# M220B.net
KiCad netlist of a schematic drawn in EAGLE
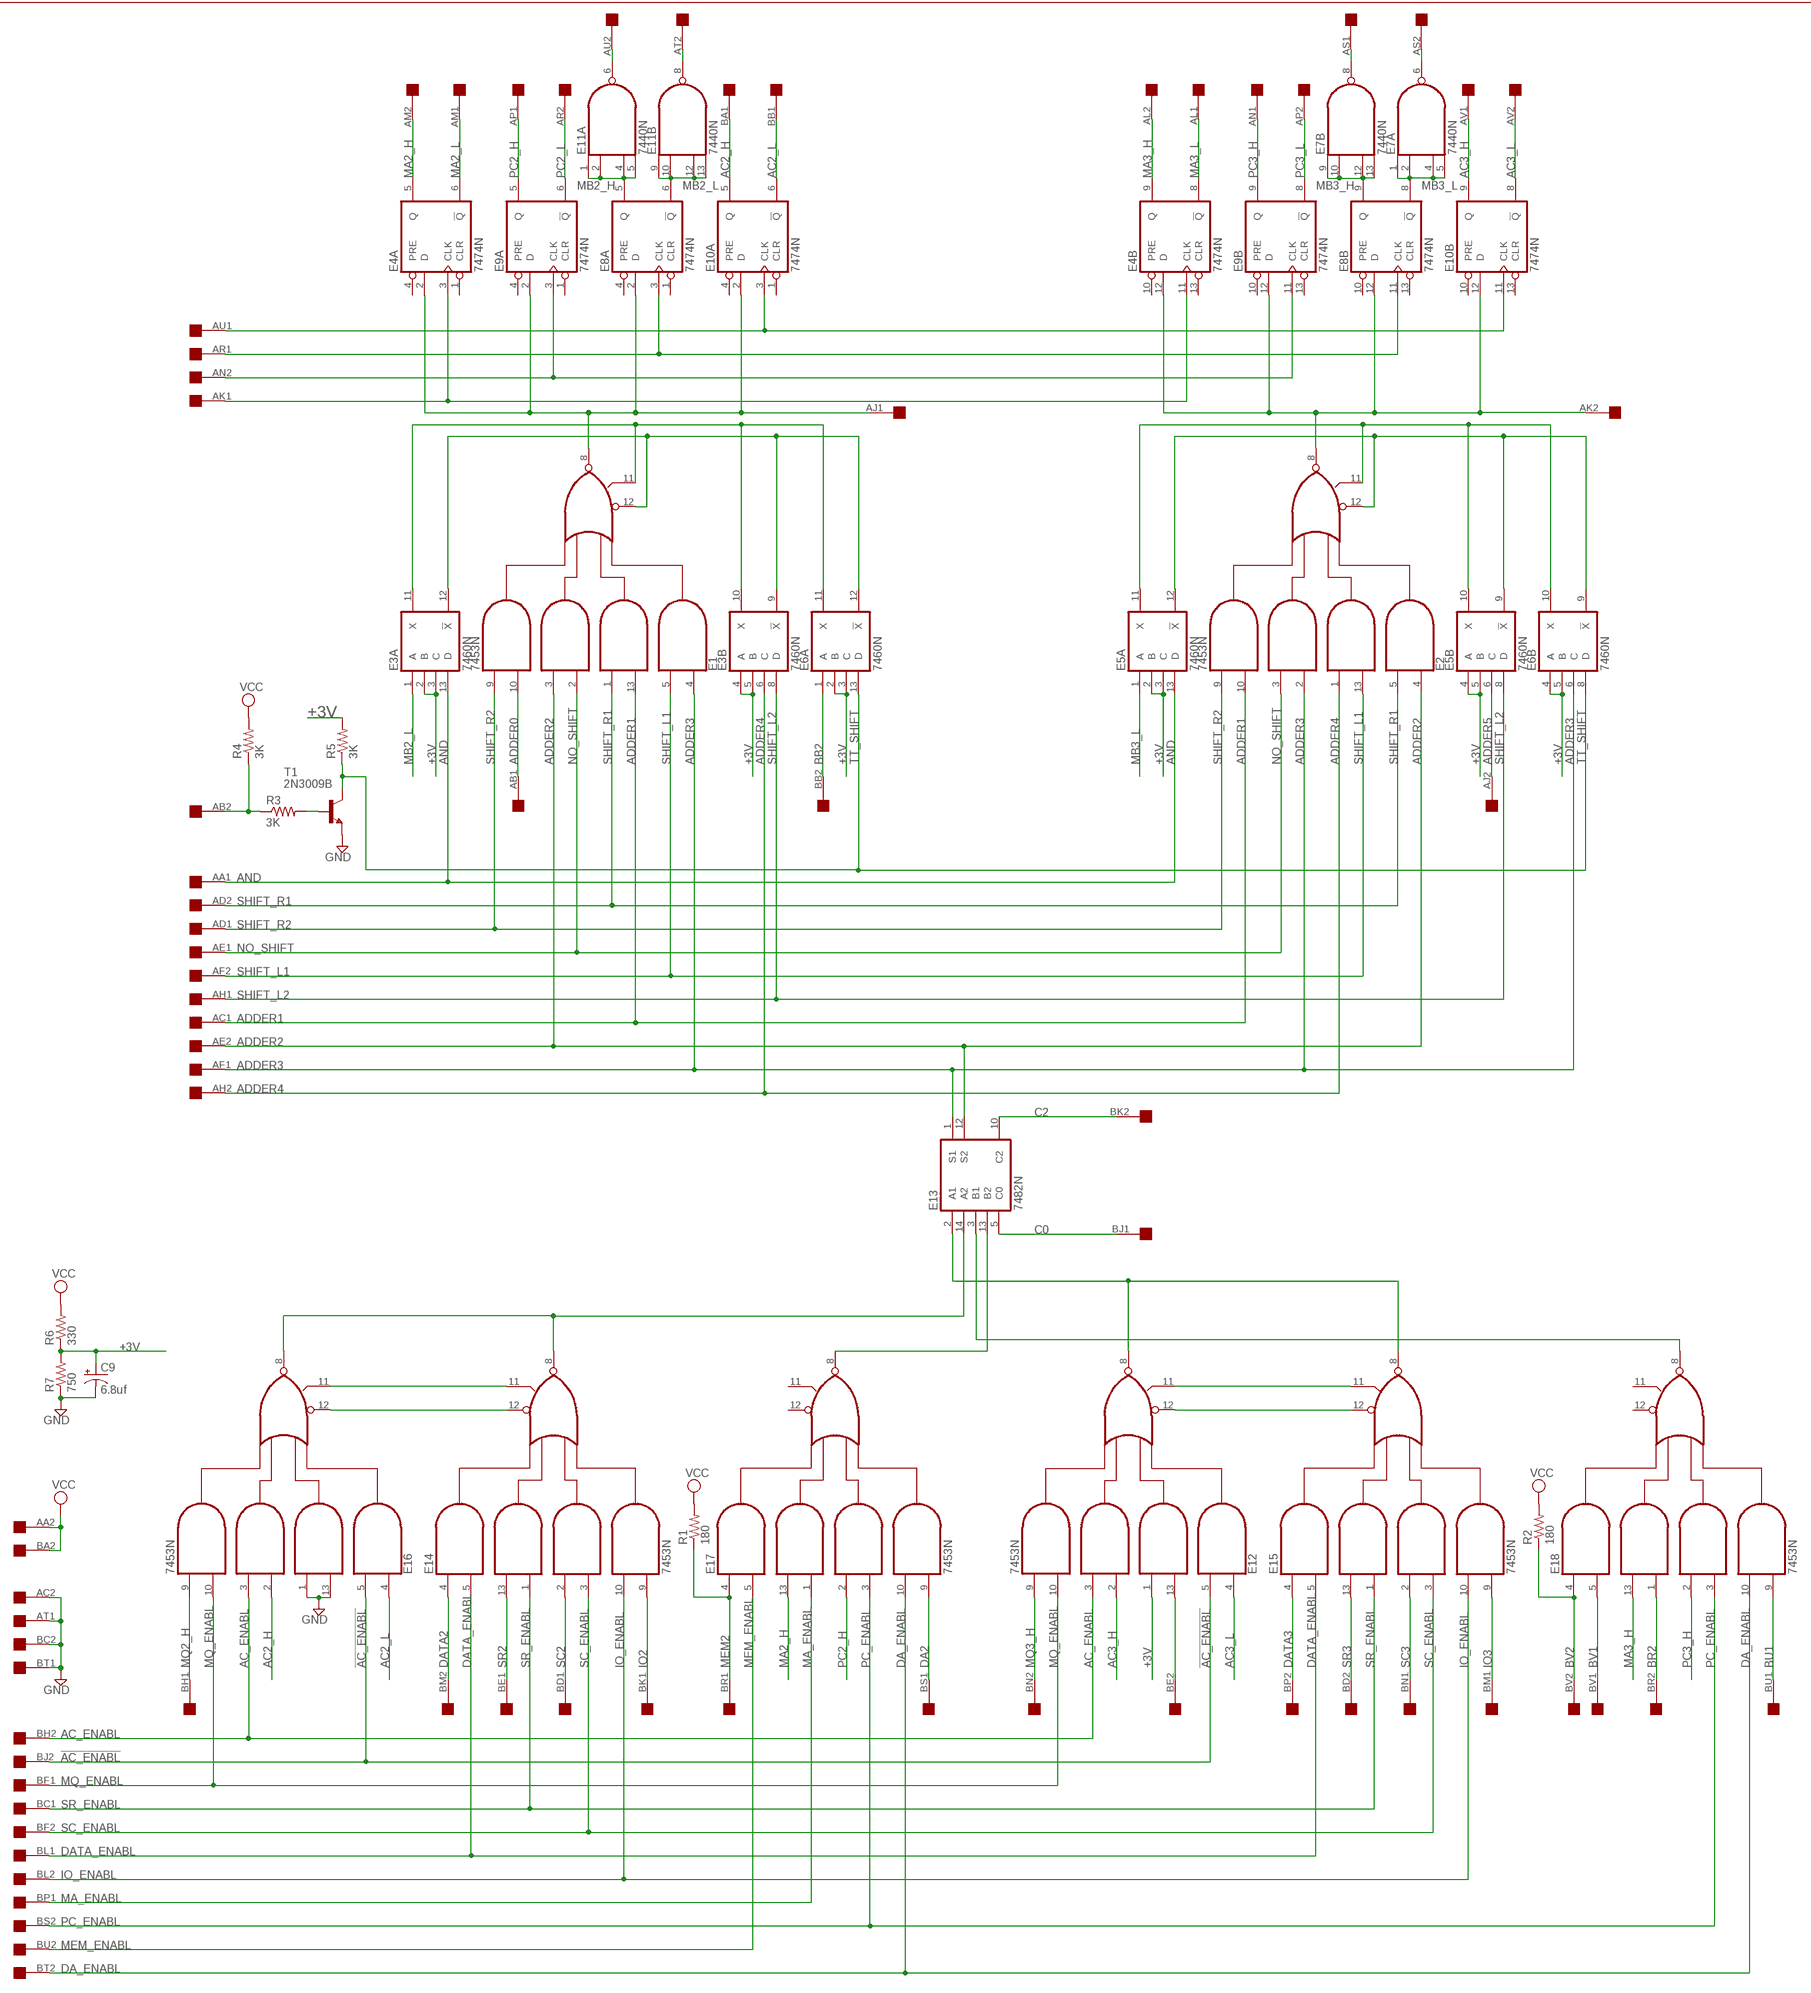
[diagram p0: schematic, sheet 1, part 1 of 2]
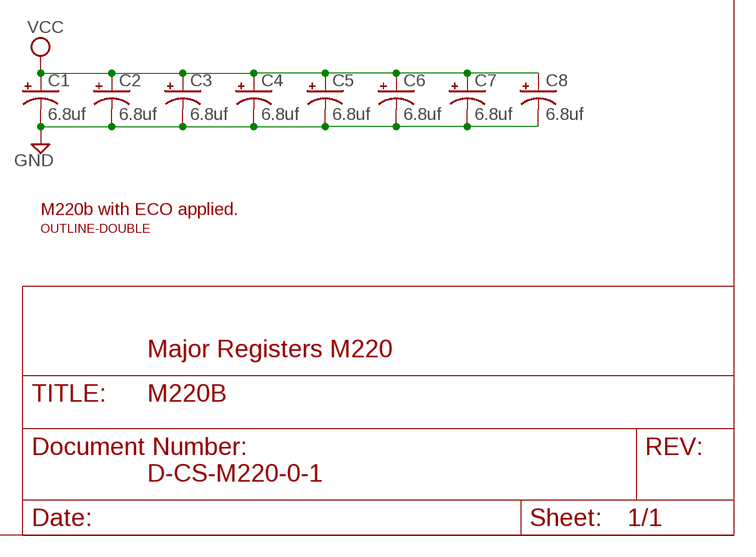
[diagram p1: schematic, sheet 1, part 2 of 2]

(export (version "E")
  (design (tool "Eeschema 10.0.6"))
  (components
    (comp (ref "C1")
      (value "6.8uf")
      (footprint "eagle-import:E15-5")
      (libsource (lib "eagle-import") (part "CPOL-USE15-5AXIAL"))
    )
    (comp (ref "C2")
      (value "6.8uf")
      (footprint "eagle-import:E15-5")
      (libsource (lib "eagle-import") (part "CPOL-USE15-5AXIAL"))
    )
    (comp (ref "C3")
      (value "6.8uf")
      (footprint "eagle-import:E15-5")
      (libsource (lib "eagle-import") (part "CPOL-USE15-5AXIAL"))
    )
    (comp (ref "C4")
      (value "6.8uf")
      (footprint "eagle-import:E15-5")
      (libsource (lib "eagle-import") (part "CPOL-USE15-5AXIAL"))
    )
    (comp (ref "C5")
      (value "6.8uf")
      (footprint "eagle-import:E15-5")
      (libsource (lib "eagle-import") (part "CPOL-USE15-5AXIAL"))
    )
    (comp (ref "C6")
      (value "6.8uf")
      (footprint "eagle-import:E15-5")
      (libsource (lib "eagle-import") (part "CPOL-USE15-5AXIAL"))
    )
    (comp (ref "C7")
      (value "6.8uf")
      (footprint "eagle-import:E15-5")
      (libsource (lib "eagle-import") (part "CPOL-USE15-5AXIAL"))
    )
    (comp (ref "C8")
      (value "6.8uf")
      (footprint "eagle-import:E15-5")
      (libsource (lib "eagle-import") (part "CPOL-USE15-5AXIAL"))
    )
    (comp (ref "C9")
      (value "6.8uf")
      (footprint "eagle-import:E15-5")
      (libsource (lib "eagle-import") (part "rcl_CPOL-USE15-5AXIAL"))
    )
    (comp (ref "E1")
      (value "7453N")
      (footprint "eagle-import:DIL14")
      (libsource (lib "eagle-import") (part "7453N"))
    )
    (comp (ref "E2")
      (value "7453N")
      (footprint "eagle-import:DIL14")
      (libsource (lib "eagle-import") (part "7453N"))
    )
    (comp (ref "E3")
      (value "7460N")
      (footprint "eagle-import:DIL14")
      (libsource (lib "eagle-import") (part "7460N"))
    )
    (comp (ref "E4")
      (value "7474N")
      (footprint "eagle-import:DIL14")
      (libsource (lib "eagle-import") (part "7474NS"))
    )
    (comp (ref "E5")
      (value "7460N")
      (footprint "eagle-import:DIL14")
      (libsource (lib "eagle-import") (part "7460N"))
    )
    (comp (ref "E6")
      (value "7460N")
      (footprint "eagle-import:DIL14")
      (libsource (lib "eagle-import") (part "7460N"))
    )
    (comp (ref "E7")
      (value "7440N")
      (footprint "eagle-import:DIL14")
      (libsource (lib "eagle-import") (part "7420NS"))
    )
    (comp (ref "E8")
      (value "7474N")
      (footprint "eagle-import:DIL14")
      (libsource (lib "eagle-import") (part "7474NS"))
    )
    (comp (ref "E9")
      (value "7474N")
      (footprint "eagle-import:DIL14")
      (libsource (lib "eagle-import") (part "7474NS"))
    )
    (comp (ref "E10")
      (value "7474N")
      (footprint "eagle-import:DIL14")
      (libsource (lib "eagle-import") (part "7474NS"))
    )
    (comp (ref "E11")
      (value "7440N")
      (footprint "eagle-import:DIL14")
      (libsource (lib "eagle-import") (part "7420NS"))
    )
    (comp (ref "E12")
      (value "7453N")
      (footprint "eagle-import:DIL14")
      (libsource (lib "eagle-import") (part "7453N"))
    )
    (comp (ref "E13")
      (value "7482N")
      (footprint "eagle-import:DIL14")
      (libsource (lib "eagle-import") (part "7482N"))
    )
    (comp (ref "E14")
      (value "7453N")
      (footprint "eagle-import:DIL14")
      (libsource (lib "eagle-import") (part "7453N"))
    )
    (comp (ref "E15")
      (value "7453N")
      (footprint "eagle-import:DIL14")
      (libsource (lib "eagle-import") (part "7453N"))
    )
    (comp (ref "E16")
      (value "7453N")
      (footprint "eagle-import:DIL14")
      (libsource (lib "eagle-import") (part "7453N"))
    )
    (comp (ref "E17")
      (value "7453N")
      (footprint "eagle-import:DIL14")
      (libsource (lib "eagle-import") (part "7453N"))
    )
    (comp (ref "E18")
      (value "7453N")
      (footprint "eagle-import:DIL14")
      (libsource (lib "eagle-import") (part "7453N"))
    )
    (comp (ref "R1")
      (value "180")
      (footprint "eagle-import:0207_10")
      (libsource (lib "eagle-import") (part "R-US_0207/10"))
    )
    (comp (ref "R2")
      (value "180")
      (footprint "eagle-import:0207_10")
      (libsource (lib "eagle-import") (part "R-US_0207/10"))
    )
    (comp (ref "R3")
      (value "3K")
      (footprint "eagle-import:0207_10")
      (libsource (lib "eagle-import") (part "R-US_0207/10"))
    )
    (comp (ref "R4")
      (value "3K")
      (footprint "eagle-import:0207_10")
      (libsource (lib "eagle-import") (part "R-US_0207/10"))
    )
    (comp (ref "R5")
      (value "3K")
      (footprint "eagle-import:0207_10")
      (libsource (lib "eagle-import") (part "R-US_0207/10"))
    )
    (comp (ref "R6")
      (value "330")
      (footprint "eagle-import:0207_10")
      (libsource (lib "eagle-import") (part "R-US_0207/10"))
    )
    (comp (ref "R7")
      (value "750")
      (footprint "eagle-import:0207_10")
      (libsource (lib "eagle-import") (part "R-US_0207/10"))
    )
    (comp (ref "T1")
      (value "2N3009B")
      (footprint "eagle-import:TO5")
      (libsource (lib "eagle-import") (part "2N1613"))
    )
    (comp (ref "U$1")
      (value "DOUBLE")
      (footprint "eagle-import:EDGE-CON4")
      (libsource (lib "eagle-import") (part "DOUBLE"))
    )
    (comp (ref "U$2")
      (value "OUTLINE-DOUBLE")
      (footprint "eagle-import:DOUBLE")
      (libsource (lib "eagle-import") (part "OUTLINE-DOUBLE"))
    )
  )
  (nets
    (net (code "1") (name "/+3V") (class "Default")
      (node (ref "C9") (pin "+") (pinfunction "+_+") (pintype "passive"))
      (node (ref "E12") (pin "1") (pinfunction "I4_1") (pintype "input"))
      (node (ref "E3") (pin "2") (pinfunction "B_2") (pintype "input"))
      (node (ref "E3") (pin "3") (pinfunction "C_3") (pintype "input"))
      (node (ref "E3") (pin "4") (pinfunction "A_4") (pintype "input"))
      (node (ref "E3") (pin "5") (pinfunction "B_5") (pintype "input"))
      (node (ref "E5") (pin "2") (pinfunction "B_2") (pintype "input"))
      (node (ref "E5") (pin "3") (pinfunction "C_3") (pintype "input"))
      (node (ref "E5") (pin "4") (pinfunction "A_4") (pintype "input"))
      (node (ref "E5") (pin "5") (pinfunction "B_5") (pintype "input"))
      (node (ref "E6") (pin "2") (pinfunction "B_2") (pintype "input"))
      (node (ref "E6") (pin "3") (pinfunction "C_3") (pintype "input"))
      (node (ref "E6") (pin "4") (pinfunction "A_4") (pintype "input"))
      (node (ref "E6") (pin "5") (pinfunction "B_5") (pintype "input"))
      (node (ref "R5") (pin "2") (pinfunction "2_2") (pintype "passive"))
      (node (ref "R6") (pin "1") (pinfunction "1_1") (pintype "passive"))
      (node (ref "R7") (pin "2") (pinfunction "2_2") (pintype "passive"))
    )
    (net (code "2") (name "/AC2_H") (class "Default")
      (node (ref "E10") (pin "5") (pinfunction "Q_5") (pintype "output"))
      (node (ref "E16") (pin "2") (pinfunction "I5_2") (pintype "input"))
      (node (ref "U$1") (pin "BA1") (pinfunction "1_BA1") (pintype "bidirectional"))
    )
    (net (code "3") (name "/AC2_L") (class "Default")
      (node (ref "E10") (pin "6") (pinfunction "~{Q}_6") (pintype "output"))
      (node (ref "E16") (pin "4") (pinfunction "I1_4") (pintype "input"))
      (node (ref "U$1") (pin "BB1") (pinfunction "1_BB1") (pintype "bidirectional"))
    )
    (net (code "4") (name "/AC3_H") (class "Default")
      (node (ref "E10") (pin "9") (pinfunction "Q_9") (pintype "output"))
      (node (ref "E12") (pin "2") (pinfunction "I5_2") (pintype "input"))
      (node (ref "U$1") (pin "AV1") (pinfunction "1_AV1") (pintype "bidirectional"))
    )
    (net (code "5") (name "/AC3_L") (class "Default")
      (node (ref "E10") (pin "8") (pinfunction "~{Q}_8") (pintype "output"))
      (node (ref "E12") (pin "4") (pinfunction "I1_4") (pintype "input"))
      (node (ref "U$1") (pin "AV2") (pinfunction "1_AV2") (pintype "bidirectional"))
    )
    (net (code "6") (name "/AC_ENABL") (class "Default")
      (node (ref "E12") (pin "3") (pinfunction "I6_3") (pintype "input"))
      (node (ref "E16") (pin "3") (pinfunction "I6_3") (pintype "input"))
      (node (ref "U$1") (pin "BH2") (pinfunction "1_BH2") (pintype "bidirectional"))
    )
    (net (code "7") (name "/ADDER0") (class "Default")
      (node (ref "E1") (pin "10") (pinfunction "I7_10") (pintype "input"))
      (node (ref "U$1") (pin "AB1") (pinfunction "1_AB1") (pintype "bidirectional"))
    )
    (net (code "8") (name "/ADDER1") (class "Default")
      (node (ref "E1") (pin "13") (pinfunction "I3_13") (pintype "input"))
      (node (ref "E2") (pin "10") (pinfunction "I7_10") (pintype "input"))
      (node (ref "U$1") (pin "AC1") (pinfunction "1_AC1") (pintype "bidirectional"))
    )
    (net (code "9") (name "/ADDER2") (class "Default")
      (node (ref "E1") (pin "3") (pinfunction "I6_3") (pintype "input"))
      (node (ref "E13") (pin "12") (pinfunction "S2_12") (pintype "output"))
      (node (ref "E2") (pin "4") (pinfunction "I1_4") (pintype "input"))
      (node (ref "U$1") (pin "AE2") (pinfunction "1_AE2") (pintype "bidirectional"))
    )
    (net (code "10") (name "/ADDER3") (class "Default")
      (node (ref "E1") (pin "4") (pinfunction "I1_4") (pintype "input"))
      (node (ref "E13") (pin "1") (pinfunction "S1_1") (pintype "output"))
      (node (ref "E2") (pin "2") (pinfunction "I5_2") (pintype "input"))
      (node (ref "E6") (pin "6") (pinfunction "C_6") (pintype "input"))
      (node (ref "U$1") (pin "AF1") (pinfunction "1_AF1") (pintype "bidirectional"))
    )
    (net (code "11") (name "/ADDER4") (class "Default")
      (node (ref "E2") (pin "1") (pinfunction "I4_1") (pintype "input"))
      (node (ref "E3") (pin "6") (pinfunction "C_6") (pintype "input"))
      (node (ref "U$1") (pin "AH2") (pinfunction "1_AH2") (pintype "bidirectional"))
    )
    (net (code "12") (name "/ADDER5") (class "Default")
      (node (ref "E5") (pin "6") (pinfunction "C_6") (pintype "input"))
      (node (ref "U$1") (pin "AJ2") (pinfunction "1_AJ2") (pintype "bidirectional"))
    )
    (net (code "13") (name "/AND") (class "Default")
      (node (ref "E3") (pin "13") (pinfunction "D_13") (pintype "input"))
      (node (ref "E5") (pin "13") (pinfunction "D_13") (pintype "input"))
      (node (ref "U$1") (pin "AA1") (pinfunction "1_AA1") (pintype "bidirectional"))
    )
    (net (code "14") (name "/BB2") (class "Default")
      (node (ref "E6") (pin "1") (pinfunction "A_1") (pintype "input"))
      (node (ref "U$1") (pin "BB2") (pinfunction "1_BB2") (pintype "bidirectional"))
    )
    (net (code "15") (name "/BR2") (class "Default")
      (node (ref "E18") (pin "1") (pinfunction "I4_1") (pintype "input"))
      (node (ref "U$1") (pin "BR2") (pinfunction "1_BR2") (pintype "bidirectional"))
    )
    (net (code "16") (name "/BU1") (class "Default")
      (node (ref "E18") (pin "9") (pinfunction "I8_9") (pintype "input"))
      (node (ref "U$1") (pin "BU1") (pinfunction "1_BU1") (pintype "bidirectional"))
    )
    (net (code "17") (name "/BV1") (class "Default")
      (node (ref "E18") (pin "5") (pinfunction "I2_5") (pintype "input"))
      (node (ref "U$1") (pin "BV1") (pinfunction "1_BV1") (pintype "bidirectional"))
    )
    (net (code "18") (name "/BV2") (class "Default")
      (node (ref "E18") (pin "4") (pinfunction "I1_4") (pintype "input"))
      (node (ref "R2") (pin "1") (pinfunction "1_1") (pintype "passive"))
      (node (ref "U$1") (pin "BV2") (pinfunction "1_BV2") (pintype "bidirectional"))
    )
    (net (code "19") (name "/C0") (class "Default")
      (node (ref "E13") (pin "5") (pinfunction "C0_5") (pintype "input"))
      (node (ref "U$1") (pin "BJ1") (pinfunction "1_BJ1") (pintype "bidirectional"))
    )
    (net (code "20") (name "/C2") (class "Default")
      (node (ref "E13") (pin "10") (pinfunction "C2_10") (pintype "output"))
      (node (ref "U$1") (pin "BK2") (pinfunction "1_BK2") (pintype "bidirectional"))
    )
    (net (code "21") (name "/DA2") (class "Default")
      (node (ref "E17") (pin "9") (pinfunction "I8_9") (pintype "input"))
      (node (ref "U$1") (pin "BS1") (pinfunction "1_BS1") (pintype "bidirectional"))
    )
    (net (code "22") (name "/DATA2") (class "Default")
      (node (ref "E14") (pin "4") (pinfunction "I1_4") (pintype "input"))
      (node (ref "U$1") (pin "BM2") (pinfunction "1_BM2") (pintype "bidirectional"))
    )
    (net (code "23") (name "/DATA3") (class "Default")
      (node (ref "E15") (pin "4") (pinfunction "I1_4") (pintype "input"))
      (node (ref "U$1") (pin "BP2") (pinfunction "1_BP2") (pintype "bidirectional"))
    )
    (net (code "24") (name "/DATA_ENABL") (class "Default")
      (node (ref "E14") (pin "5") (pinfunction "I2_5") (pintype "input"))
      (node (ref "E15") (pin "5") (pinfunction "I2_5") (pintype "input"))
      (node (ref "U$1") (pin "BL1") (pinfunction "1_BL1") (pintype "bidirectional"))
    )
    (net (code "25") (name "/DA_ENABL") (class "Default")
      (node (ref "E17") (pin "10") (pinfunction "I7_10") (pintype "input"))
      (node (ref "E18") (pin "10") (pinfunction "I7_10") (pintype "input"))
      (node (ref "U$1") (pin "BT2") (pinfunction "1_BT2") (pintype "bidirectional"))
    )
    (net (code "26") (name "/IO2") (class "Default")
      (node (ref "E14") (pin "9") (pinfunction "I8_9") (pintype "input"))
      (node (ref "U$1") (pin "BK1") (pinfunction "1_BK1") (pintype "bidirectional"))
    )
    (net (code "27") (name "/IO3") (class "Default")
      (node (ref "E15") (pin "9") (pinfunction "I8_9") (pintype "input"))
      (node (ref "U$1") (pin "BM1") (pinfunction "1_BM1") (pintype "bidirectional"))
    )
    (net (code "28") (name "/IO_ENABL") (class "Default")
      (node (ref "E14") (pin "10") (pinfunction "I7_10") (pintype "input"))
      (node (ref "E15") (pin "10") (pinfunction "I7_10") (pintype "input"))
      (node (ref "U$1") (pin "BL2") (pinfunction "1_BL2") (pintype "bidirectional"))
    )
    (net (code "29") (name "/MA2_H") (class "Default")
      (node (ref "E17") (pin "13") (pinfunction "I3_13") (pintype "input"))
      (node (ref "E4") (pin "5") (pinfunction "Q_5") (pintype "output"))
      (node (ref "U$1") (pin "AM2") (pinfunction "1_AM2") (pintype "bidirectional"))
    )
    (net (code "30") (name "/MA2_L") (class "Default")
      (node (ref "E4") (pin "6") (pinfunction "~{Q}_6") (pintype "output"))
      (node (ref "U$1") (pin "AM1") (pinfunction "1_AM1") (pintype "bidirectional"))
    )
    (net (code "31") (name "/MA3_H") (class "Default")
      (node (ref "E18") (pin "13") (pinfunction "I3_13") (pintype "input"))
      (node (ref "E4") (pin "9") (pinfunction "Q_9") (pintype "output"))
      (node (ref "U$1") (pin "AL2") (pinfunction "1_AL2") (pintype "bidirectional"))
    )
    (net (code "32") (name "/MA3_L") (class "Default")
      (node (ref "E4") (pin "8") (pinfunction "~{Q}_8") (pintype "output"))
      (node (ref "U$1") (pin "AL1") (pinfunction "1_AL1") (pintype "bidirectional"))
    )
    (net (code "33") (name "/MA_ENABL") (class "Default")
      (node (ref "E17") (pin "1") (pinfunction "I4_1") (pintype "input"))
      (node (ref "U$1") (pin "BP1") (pinfunction "1_BP1") (pintype "bidirectional"))
    )
    (net (code "34") (name "/MB2_H") (class "Default")
      (node (ref "E11") (pin "1") (pinfunction "I0_1") (pintype "input"))
      (node (ref "E11") (pin "2") (pinfunction "I1_2") (pintype "input"))
      (node (ref "E11") (pin "4") (pinfunction "I2_4") (pintype "input"))
      (node (ref "E11") (pin "5") (pinfunction "I3_5") (pintype "input"))
      (node (ref "E8") (pin "5") (pinfunction "Q_5") (pintype "output"))
    )
    (net (code "35") (name "/MB2_L") (class "Default")
      (node (ref "E11") (pin "10") (pinfunction "I1_10") (pintype "input"))
      (node (ref "E11") (pin "12") (pinfunction "I2_12") (pintype "input"))
      (node (ref "E11") (pin "13") (pinfunction "I3_13") (pintype "input"))
      (node (ref "E11") (pin "9") (pinfunction "I0_9") (pintype "input"))
      (node (ref "E3") (pin "1") (pinfunction "A_1") (pintype "input"))
      (node (ref "E8") (pin "6") (pinfunction "~{Q}_6") (pintype "output"))
    )
    (net (code "36") (name "/MB3_H") (class "Default")
      (node (ref "E7") (pin "10") (pinfunction "I1_10") (pintype "input"))
      (node (ref "E7") (pin "12") (pinfunction "I2_12") (pintype "input"))
      (node (ref "E7") (pin "13") (pinfunction "I3_13") (pintype "input"))
      (node (ref "E7") (pin "9") (pinfunction "I0_9") (pintype "input"))
      (node (ref "E8") (pin "9") (pinfunction "Q_9") (pintype "output"))
    )
    (net (code "37") (name "/MB3_L") (class "Default")
      (node (ref "E5") (pin "1") (pinfunction "A_1") (pintype "input"))
      (node (ref "E7") (pin "1") (pinfunction "I0_1") (pintype "input"))
      (node (ref "E7") (pin "2") (pinfunction "I1_2") (pintype "input"))
      (node (ref "E7") (pin "4") (pinfunction "I2_4") (pintype "input"))
      (node (ref "E7") (pin "5") (pinfunction "I3_5") (pintype "input"))
      (node (ref "E8") (pin "8") (pinfunction "~{Q}_8") (pintype "output"))
    )
    (net (code "38") (name "/MEM2") (class "Default")
      (node (ref "E17") (pin "4") (pinfunction "I1_4") (pintype "input"))
      (node (ref "R1") (pin "1") (pinfunction "1_1") (pintype "passive"))
      (node (ref "U$1") (pin "BR1") (pinfunction "1_BR1") (pintype "bidirectional"))
    )
    (net (code "39") (name "/MEM_ENABL") (class "Default")
      (node (ref "E17") (pin "5") (pinfunction "I2_5") (pintype "input"))
      (node (ref "U$1") (pin "BU2") (pinfunction "1_BU2") (pintype "bidirectional"))
    )
    (net (code "40") (name "/MQ2_H") (class "Default")
      (node (ref "E16") (pin "9") (pinfunction "I8_9") (pintype "input"))
      (node (ref "U$1") (pin "BH1") (pinfunction "1_BH1") (pintype "bidirectional"))
    )
    (net (code "41") (name "/MQ3_H") (class "Default")
      (node (ref "E12") (pin "9") (pinfunction "I8_9") (pintype "input"))
      (node (ref "U$1") (pin "BN2") (pinfunction "1_BN2") (pintype "bidirectional"))
    )
    (net (code "42") (name "/MQ_ENABL") (class "Default")
      (node (ref "E12") (pin "10") (pinfunction "I7_10") (pintype "input"))
      (node (ref "E16") (pin "10") (pinfunction "I7_10") (pintype "input"))
      (node (ref "U$1") (pin "BF1") (pinfunction "1_BF1") (pintype "bidirectional"))
    )
    (net (code "43") (name "/NO_SHIFT") (class "Default")
      (node (ref "E1") (pin "2") (pinfunction "I5_2") (pintype "input"))
      (node (ref "E2") (pin "3") (pinfunction "I6_3") (pintype "input"))
      (node (ref "U$1") (pin "AE1") (pinfunction "1_AE1") (pintype "bidirectional"))
    )
    (net (code "44") (name "/PC2_H") (class "Default")
      (node (ref "E17") (pin "2") (pinfunction "I5_2") (pintype "input"))
      (node (ref "E9") (pin "5") (pinfunction "Q_5") (pintype "output"))
      (node (ref "U$1") (pin "AP1") (pinfunction "1_AP1") (pintype "bidirectional"))
    )
    (net (code "45") (name "/PC2_L") (class "Default")
      (node (ref "E9") (pin "6") (pinfunction "~{Q}_6") (pintype "output"))
      (node (ref "U$1") (pin "AR2") (pinfunction "1_AR2") (pintype "bidirectional"))
    )
    (net (code "46") (name "/PC3_H") (class "Default")
      (node (ref "E18") (pin "2") (pinfunction "I5_2") (pintype "input"))
      (node (ref "E9") (pin "9") (pinfunction "Q_9") (pintype "output"))
      (node (ref "U$1") (pin "AN1") (pinfunction "1_AN1") (pintype "bidirectional"))
    )
    (net (code "47") (name "/PC3_L") (class "Default")
      (node (ref "E9") (pin "8") (pinfunction "~{Q}_8") (pintype "output"))
      (node (ref "U$1") (pin "AP2") (pinfunction "1_AP2") (pintype "bidirectional"))
    )
    (net (code "48") (name "/PC_ENABL") (class "Default")
      (node (ref "E17") (pin "3") (pinfunction "I6_3") (pintype "input"))
      (node (ref "E18") (pin "3") (pinfunction "I6_3") (pintype "input"))
      (node (ref "U$1") (pin "BS2") (pinfunction "1_BS2") (pintype "bidirectional"))
    )
    (net (code "49") (name "/SC2") (class "Default")
      (node (ref "E14") (pin "2") (pinfunction "I5_2") (pintype "input"))
      (node (ref "U$1") (pin "BD1") (pinfunction "1_BD1") (pintype "bidirectional"))
    )
    (net (code "50") (name "/SC3") (class "Default")
      (node (ref "E15") (pin "2") (pinfunction "I5_2") (pintype "input"))
      (node (ref "U$1") (pin "BN1") (pinfunction "1_BN1") (pintype "bidirectional"))
    )
    (net (code "51") (name "/SC_ENABL") (class "Default")
      (node (ref "E14") (pin "3") (pinfunction "I6_3") (pintype "input"))
      (node (ref "E15") (pin "3") (pinfunction "I6_3") (pintype "input"))
      (node (ref "U$1") (pin "BF2") (pinfunction "1_BF2") (pintype "bidirectional"))
    )
    (net (code "52") (name "/SHIFT_L1") (class "Default")
      (node (ref "E1") (pin "5") (pinfunction "I2_5") (pintype "input"))
      (node (ref "E2") (pin "13") (pinfunction "I3_13") (pintype "input"))
      (node (ref "U$1") (pin "AF2") (pinfunction "1_AF2") (pintype "bidirectional"))
    )
    (net (code "53") (name "/SHIFT_L2") (class "Default")
      (node (ref "E3") (pin "8") (pinfunction "D_8") (pintype "input"))
      (node (ref "E5") (pin "8") (pinfunction "D_8") (pintype "input"))
      (node (ref "U$1") (pin "AH1") (pinfunction "1_AH1") (pintype "bidirectional"))
    )
    (net (code "54") (name "/SHIFT_R1") (class "Default")
      (node (ref "E1") (pin "1") (pinfunction "I4_1") (pintype "input"))
      (node (ref "E2") (pin "5") (pinfunction "I2_5") (pintype "input"))
      (node (ref "U$1") (pin "AD2") (pinfunction "1_AD2") (pintype "bidirectional"))
    )
    (net (code "55") (name "/SHIFT_R2") (class "Default")
      (node (ref "E1") (pin "9") (pinfunction "I8_9") (pintype "input"))
      (node (ref "E2") (pin "9") (pinfunction "I8_9") (pintype "input"))
      (node (ref "U$1") (pin "AD1") (pinfunction "1_AD1") (pintype "bidirectional"))
    )
    (net (code "56") (name "/SR2") (class "Default")
      (node (ref "E14") (pin "13") (pinfunction "I3_13") (pintype "input"))
      (node (ref "U$1") (pin "BE1") (pinfunction "1_BE1") (pintype "bidirectional"))
    )
    (net (code "57") (name "/SR3") (class "Default")
      (node (ref "E15") (pin "13") (pinfunction "I3_13") (pintype "input"))
      (node (ref "U$1") (pin "BD2") (pinfunction "1_BD2") (pintype "bidirectional"))
    )
    (net (code "58") (name "/SR_ENABL") (class "Default")
      (node (ref "E14") (pin "1") (pinfunction "I4_1") (pintype "input"))
      (node (ref "E15") (pin "1") (pinfunction "I4_1") (pintype "input"))
      (node (ref "U$1") (pin "BC1") (pinfunction "1_BC1") (pintype "bidirectional"))
    )
    (net (code "59") (name "/TT_SHIFT") (class "Default")
      (node (ref "E6") (pin "13") (pinfunction "D_13") (pintype "input"))
      (node (ref "E6") (pin "8") (pinfunction "D_8") (pintype "input"))
      (node (ref "R5") (pin "1") (pinfunction "1_1") (pintype "passive"))
      (node (ref "T1") (pin "3") (pinfunction "C_3") (pintype "passive"))
    )
    (net (code "60") (name "/~{AC_ENABL}") (class "Default")
      (node (ref "E12") (pin "5") (pinfunction "I2_5") (pintype "input"))
      (node (ref "E16") (pin "5") (pinfunction "I2_5") (pintype "input"))
      (node (ref "U$1") (pin "BJ2") (pinfunction "1_BJ2") (pintype "bidirectional"))
    )
    (net (code "61") (name "GND") (class "Default")
      (node (ref "C1") (pin "-") (pinfunction "-_-") (pintype "passive"))
      (node (ref "C2") (pin "-") (pinfunction "-_-") (pintype "passive"))
      (node (ref "C3") (pin "-") (pinfunction "-_-") (pintype "passive"))
      (node (ref "C4") (pin "-") (pinfunction "-_-") (pintype "passive"))
      (node (ref "C5") (pin "-") (pinfunction "-_-") (pintype "passive"))
      (node (ref "C6") (pin "-") (pinfunction "-_-") (pintype "passive"))
      (node (ref "C7") (pin "-") (pinfunction "-_-") (pintype "passive"))
      (node (ref "C8") (pin "-") (pinfunction "-_-") (pintype "passive"))
      (node (ref "C9") (pin "-") (pinfunction "-_-") (pintype "passive"))
      (node (ref "E16") (pin "1") (pinfunction "I4_1") (pintype "input"))
      (node (ref "E16") (pin "13") (pinfunction "I3_13") (pintype "input"))
      (node (ref "R7") (pin "1") (pinfunction "1_1") (pintype "passive"))
      (node (ref "T1") (pin "1") (pinfunction "E_1") (pintype "passive"))
      (node (ref "U$1") (pin "AC2") (pinfunction "1_AC2") (pintype "bidirectional"))
      (node (ref "U$1") (pin "AT1") (pinfunction "1_AT1") (pintype "bidirectional"))
      (node (ref "U$1") (pin "BC2") (pinfunction "1_BC2") (pintype "bidirectional"))
      (node (ref "U$1") (pin "BT1") (pinfunction "1_BT1") (pintype "bidirectional"))
    )
    (net (code "62") (name "Net-(E1A-I9)") (class "Default")
      (node (ref "E1") (pin "12") (pinfunction "I9_12") (pintype "passive"))
      (node (ref "E3") (pin "12") (pinfunction "~{X}_12") (pintype "output"))
      (node (ref "E3") (pin "9") (pinfunction "~{X}_9") (pintype "output"))
      (node (ref "E6") (pin "12") (pinfunction "~{X}_12") (pintype "output"))
    )
    (net (code "63") (name "Net-(E1A-I10)") (class "Default")
      (node (ref "E1") (pin "11") (pinfunction "I10_11") (pintype "passive"))
      (node (ref "E3") (pin "10") (pinfunction "X_10") (pintype "output"))
      (node (ref "E3") (pin "11") (pinfunction "X_11") (pintype "output"))
      (node (ref "E6") (pin "11") (pinfunction "X_11") (pintype "output"))
    )
    (net (code "64") (name "Net-(E2A-I9)") (class "Default")
      (node (ref "E2") (pin "12") (pinfunction "I9_12") (pintype "passive"))
      (node (ref "E5") (pin "12") (pinfunction "~{X}_12") (pintype "output"))
      (node (ref "E5") (pin "9") (pinfunction "~{X}_9") (pintype "output"))
      (node (ref "E6") (pin "9") (pinfunction "~{X}_9") (pintype "output"))
    )
    (net (code "65") (name "Net-(E2A-I10)") (class "Default")
      (node (ref "E2") (pin "11") (pinfunction "I10_11") (pintype "passive"))
      (node (ref "E5") (pin "10") (pinfunction "X_10") (pintype "output"))
      (node (ref "E5") (pin "11") (pinfunction "X_11") (pintype "output"))
      (node (ref "E6") (pin "10") (pinfunction "X_10") (pintype "output"))
    )
    (net (code "66") (name "Net-(E4A-CLK)") (class "Default")
      (node (ref "E4") (pin "11") (pinfunction "CLK_11") (pintype "input"))
      (node (ref "E4") (pin "3") (pinfunction "CLK_3") (pintype "input"))
      (node (ref "U$1") (pin "AK1") (pinfunction "1_AK1") (pintype "bidirectional"))
    )
    (net (code "67") (name "Net-(E7A-O)") (class "Default")
      (node (ref "E7") (pin "6") (pinfunction "O_6") (pintype "output"))
      (node (ref "U$1") (pin "AS2") (pinfunction "1_AS2") (pintype "bidirectional"))
    )
    (net (code "68") (name "Net-(E7B-O)") (class "Default")
      (node (ref "E7") (pin "8") (pinfunction "O_8") (pintype "output"))
      (node (ref "U$1") (pin "AS1") (pinfunction "1_AS1") (pintype "bidirectional"))
    )
    (net (code "69") (name "Net-(E8A-CLK)") (class "Default")
      (node (ref "E8") (pin "11") (pinfunction "CLK_11") (pintype "input"))
      (node (ref "E8") (pin "3") (pinfunction "CLK_3") (pintype "input"))
      (node (ref "U$1") (pin "AR1") (pinfunction "1_AR1") (pintype "bidirectional"))
    )
    (net (code "70") (name "Net-(E9A-CLK)") (class "Default")
      (node (ref "E9") (pin "11") (pinfunction "CLK_11") (pintype "input"))
      (node (ref "E9") (pin "3") (pinfunction "CLK_3") (pintype "input"))
      (node (ref "U$1") (pin "AN2") (pinfunction "1_AN2") (pintype "bidirectional"))
    )
    (net (code "71") (name "Net-(E10A-CLK)") (class "Default")
      (node (ref "E10") (pin "11") (pinfunction "CLK_11") (pintype "input"))
      (node (ref "E10") (pin "3") (pinfunction "CLK_3") (pintype "input"))
      (node (ref "U$1") (pin "AU1") (pinfunction "1_AU1") (pintype "bidirectional"))
    )
    (net (code "72") (name "Net-(E10A-D)") (class "Default")
      (node (ref "E1") (pin "8") (pinfunction "O_8") (pintype "output"))
      (node (ref "E10") (pin "2") (pinfunction "D_2") (pintype "input"))
      (node (ref "E4") (pin "2") (pinfunction "D_2") (pintype "input"))
      (node (ref "E8") (pin "2") (pinfunction "D_2") (pintype "input"))
      (node (ref "E9") (pin "2") (pinfunction "D_2") (pintype "input"))
      (node (ref "U$1") (pin "AJ1") (pinfunction "1_AJ1") (pintype "bidirectional"))
    )
    (net (code "73") (name "Net-(E10B-D)") (class "Default")
      (node (ref "E10") (pin "12") (pinfunction "D_12") (pintype "input"))
      (node (ref "E2") (pin "8") (pinfunction "O_8") (pintype "output"))
      (node (ref "E4") (pin "12") (pinfunction "D_12") (pintype "input"))
      (node (ref "E8") (pin "12") (pinfunction "D_12") (pintype "input"))
      (node (ref "E9") (pin "12") (pinfunction "D_12") (pintype "input"))
      (node (ref "U$1") (pin "AK2") (pinfunction "1_AK2") (pintype "bidirectional"))
    )
    (net (code "74") (name "Net-(E11A-O)") (class "Default")
      (node (ref "E11") (pin "6") (pinfunction "O_6") (pintype "output"))
      (node (ref "U$1") (pin "AU2") (pinfunction "1_AU2") (pintype "bidirectional"))
    )
    (net (code "75") (name "Net-(E11B-O)") (class "Default")
      (node (ref "E11") (pin "8") (pinfunction "O_8") (pintype "output"))
      (node (ref "U$1") (pin "AT2") (pinfunction "1_AT2") (pintype "bidirectional"))
    )
    (net (code "76") (name "Net-(E12A-I3)") (class "Default")
      (node (ref "E12") (pin "13") (pinfunction "I3_13") (pintype "input"))
      (node (ref "U$1") (pin "BE2") (pinfunction "1_BE2") (pintype "bidirectional"))
    )
    (net (code "77") (name "Net-(E12A-I9)") (class "Default")
      (node (ref "E12") (pin "12") (pinfunction "I9_12") (pintype "passive"))
      (node (ref "E15") (pin "12") (pinfunction "I9_12") (pintype "passive"))
    )
    (net (code "78") (name "Net-(E12A-I10)") (class "Default")
      (node (ref "E12") (pin "11") (pinfunction "I10_11") (pintype "passive"))
      (node (ref "E15") (pin "11") (pinfunction "I10_11") (pintype "passive"))
    )
    (net (code "79") (name "Net-(E12A-O)") (class "Default")
      (node (ref "E12") (pin "8") (pinfunction "O_8") (pintype "output"))
      (node (ref "E13") (pin "2") (pinfunction "A1_2") (pintype "input"))
      (node (ref "E15") (pin "8") (pinfunction "O_8") (pintype "output"))
    )
    (net (code "80") (name "Net-(E13E-A2)") (class "Default")
      (node (ref "E13") (pin "14") (pinfunction "A2_14") (pintype "input"))
      (node (ref "E14") (pin "8") (pinfunction "O_8") (pintype "output"))
      (node (ref "E16") (pin "8") (pinfunction "O_8") (pintype "output"))
    )
    (net (code "81") (name "Net-(E13E-B1)") (class "Default")
      (node (ref "E13") (pin "3") (pinfunction "B1_3") (pintype "input"))
      (node (ref "E18") (pin "8") (pinfunction "O_8") (pintype "output"))
    )
    (net (code "82") (name "Net-(E13E-B2)") (class "Default")
      (node (ref "E13") (pin "13") (pinfunction "B2_13") (pintype "input"))
      (node (ref "E17") (pin "8") (pinfunction "O_8") (pintype "output"))
    )
    (net (code "83") (name "Net-(E14A-I9)") (class "Default")
      (node (ref "E14") (pin "12") (pinfunction "I9_12") (pintype "passive"))
      (node (ref "E16") (pin "12") (pinfunction "I9_12") (pintype "passive"))
    )
    (net (code "84") (name "Net-(E14A-I10)") (class "Default")
      (node (ref "E14") (pin "11") (pinfunction "I10_11") (pintype "passive"))
      (node (ref "E16") (pin "11") (pinfunction "I10_11") (pintype "passive"))
    )
    (net (code "85") (name "Net-(T1-B)") (class "Default")
      (node (ref "R3") (pin "2") (pinfunction "2_2") (pintype "passive"))
      (node (ref "T1") (pin "2") (pinfunction "B_2") (pintype "passive"))
    )
    (net (code "86") (name "Net-(U$1D-1)") (class "Default")
      (node (ref "R3") (pin "1") (pinfunction "1_1") (pintype "passive"))
      (node (ref "R4") (pin "1") (pinfunction "1_1") (pintype "passive"))
      (node (ref "U$1") (pin "AB2") (pinfunction "1_AB2") (pintype "bidirectional"))
    )
    (net (code "87") (name "VCC") (class "Default")
      (node (ref "C1") (pin "+") (pinfunction "+_+") (pintype "passive"))
      (node (ref "C2") (pin "+") (pinfunction "+_+") (pintype "passive"))
      (node (ref "C3") (pin "+") (pinfunction "+_+") (pintype "passive"))
      (node (ref "C4") (pin "+") (pinfunction "+_+") (pintype "passive"))
      (node (ref "C5") (pin "+") (pinfunction "+_+") (pintype "passive"))
      (node (ref "C6") (pin "+") (pinfunction "+_+") (pintype "passive"))
      (node (ref "C7") (pin "+") (pinfunction "+_+") (pintype "passive"))
      (node (ref "C8") (pin "+") (pinfunction "+_+") (pintype "passive"))
      (node (ref "R1") (pin "2") (pinfunction "2_2") (pintype "passive"))
      (node (ref "R2") (pin "2") (pinfunction "2_2") (pintype "passive"))
      (node (ref "R4") (pin "2") (pinfunction "2_2") (pintype "passive"))
      (node (ref "R6") (pin "2") (pinfunction "2_2") (pintype "passive"))
      (node (ref "U$1") (pin "AA2") (pinfunction "1_AA2") (pintype "bidirectional"))
      (node (ref "U$1") (pin "BA2") (pinfunction "1_BA2") (pintype "bidirectional"))
    )
    (net (code "88") (name "unconnected-(E4A-CLR-Pad1)") (class "Default")
      (node (ref "E4") (pin "1") (pinfunction "CLR_1") (pintype "input"))
    )
    (net (code "89") (name "unconnected-(E4A-PRE-Pad4)") (class "Default")
      (node (ref "E4") (pin "4") (pinfunction "PRE_4") (pintype "input"))
    )
    (net (code "90") (name "unconnected-(E4B-CLR-Pad13)") (class "Default")
      (node (ref "E4") (pin "13") (pinfunction "CLR_13") (pintype "input"))
    )
    (net (code "91") (name "unconnected-(E4B-PRE-Pad10)") (class "Default")
      (node (ref "E4") (pin "10") (pinfunction "PRE_10") (pintype "input"))
    )
    (net (code "92") (name "unconnected-(E8A-CLR-Pad1)") (class "Default")
      (node (ref "E8") (pin "1") (pinfunction "CLR_1") (pintype "input"))
    )
    (net (code "93") (name "unconnected-(E8A-PRE-Pad4)") (class "Default")
      (node (ref "E8") (pin "4") (pinfunction "PRE_4") (pintype "input"))
    )
    (net (code "94") (name "unconnected-(E8B-CLR-Pad13)") (class "Default")
      (node (ref "E8") (pin "13") (pinfunction "CLR_13") (pintype "input"))
    )
    (net (code "95") (name "unconnected-(E8B-PRE-Pad10)") (class "Default")
      (node (ref "E8") (pin "10") (pinfunction "PRE_10") (pintype "input"))
    )
    (net (code "96") (name "unconnected-(E9A-CLR-Pad1)") (class "Default")
      (node (ref "E9") (pin "1") (pinfunction "CLR_1") (pintype "input"))
    )
    (net (code "97") (name "unconnected-(E9A-PRE-Pad4)") (class "Default")
      (node (ref "E9") (pin "4") (pinfunction "PRE_4") (pintype "input"))
    )
    (net (code "98") (name "unconnected-(E9B-CLR-Pad13)") (class "Default")
      (node (ref "E9") (pin "13") (pinfunction "CLR_13") (pintype "input"))
    )
    (net (code "99") (name "unconnected-(E9B-PRE-Pad10)") (class "Default")
      (node (ref "E9") (pin "10") (pinfunction "PRE_10") (pintype "input"))
    )
    (net (code "100") (name "unconnected-(E10A-CLR-Pad1)") (class "Default")
      (node (ref "E10") (pin "1") (pinfunction "CLR_1") (pintype "input"))
    )
    (net (code "101") (name "unconnected-(E10A-PRE-Pad4)") (class "Default")
      (node (ref "E10") (pin "4") (pinfunction "PRE_4") (pintype "input"))
    )
    (net (code "102") (name "unconnected-(E10B-CLR-Pad13)") (class "Default")
      (node (ref "E10") (pin "13") (pinfunction "CLR_13") (pintype "input"))
    )
    (net (code "103") (name "unconnected-(E10B-PRE-Pad10)") (class "Default")
      (node (ref "E10") (pin "10") (pinfunction "PRE_10") (pintype "input"))
    )
    (net (code "104") (name "unconnected-(E17A-I9-Pad12)") (class "Default")
      (node (ref "E17") (pin "12") (pinfunction "I9_12") (pintype "passive"))
    )
    (net (code "105") (name "unconnected-(E17A-I10-Pad11)") (class "Default")
      (node (ref "E17") (pin "11") (pinfunction "I10_11") (pintype "passive"))
    )
    (net (code "106") (name "unconnected-(E18A-I9-Pad12)") (class "Default")
      (node (ref "E18") (pin "12") (pinfunction "I9_12") (pintype "passive"))
    )
    (net (code "107") (name "unconnected-(E18A-I10-Pad11)") (class "Default")
      (node (ref "E18") (pin "11") (pinfunction "I10_11") (pintype "passive"))
    )
  )
)
